# Cargador_RasPi-BplusHAT_CamSlot.net
KiCad netlist of a schematic drawn in EAGLE
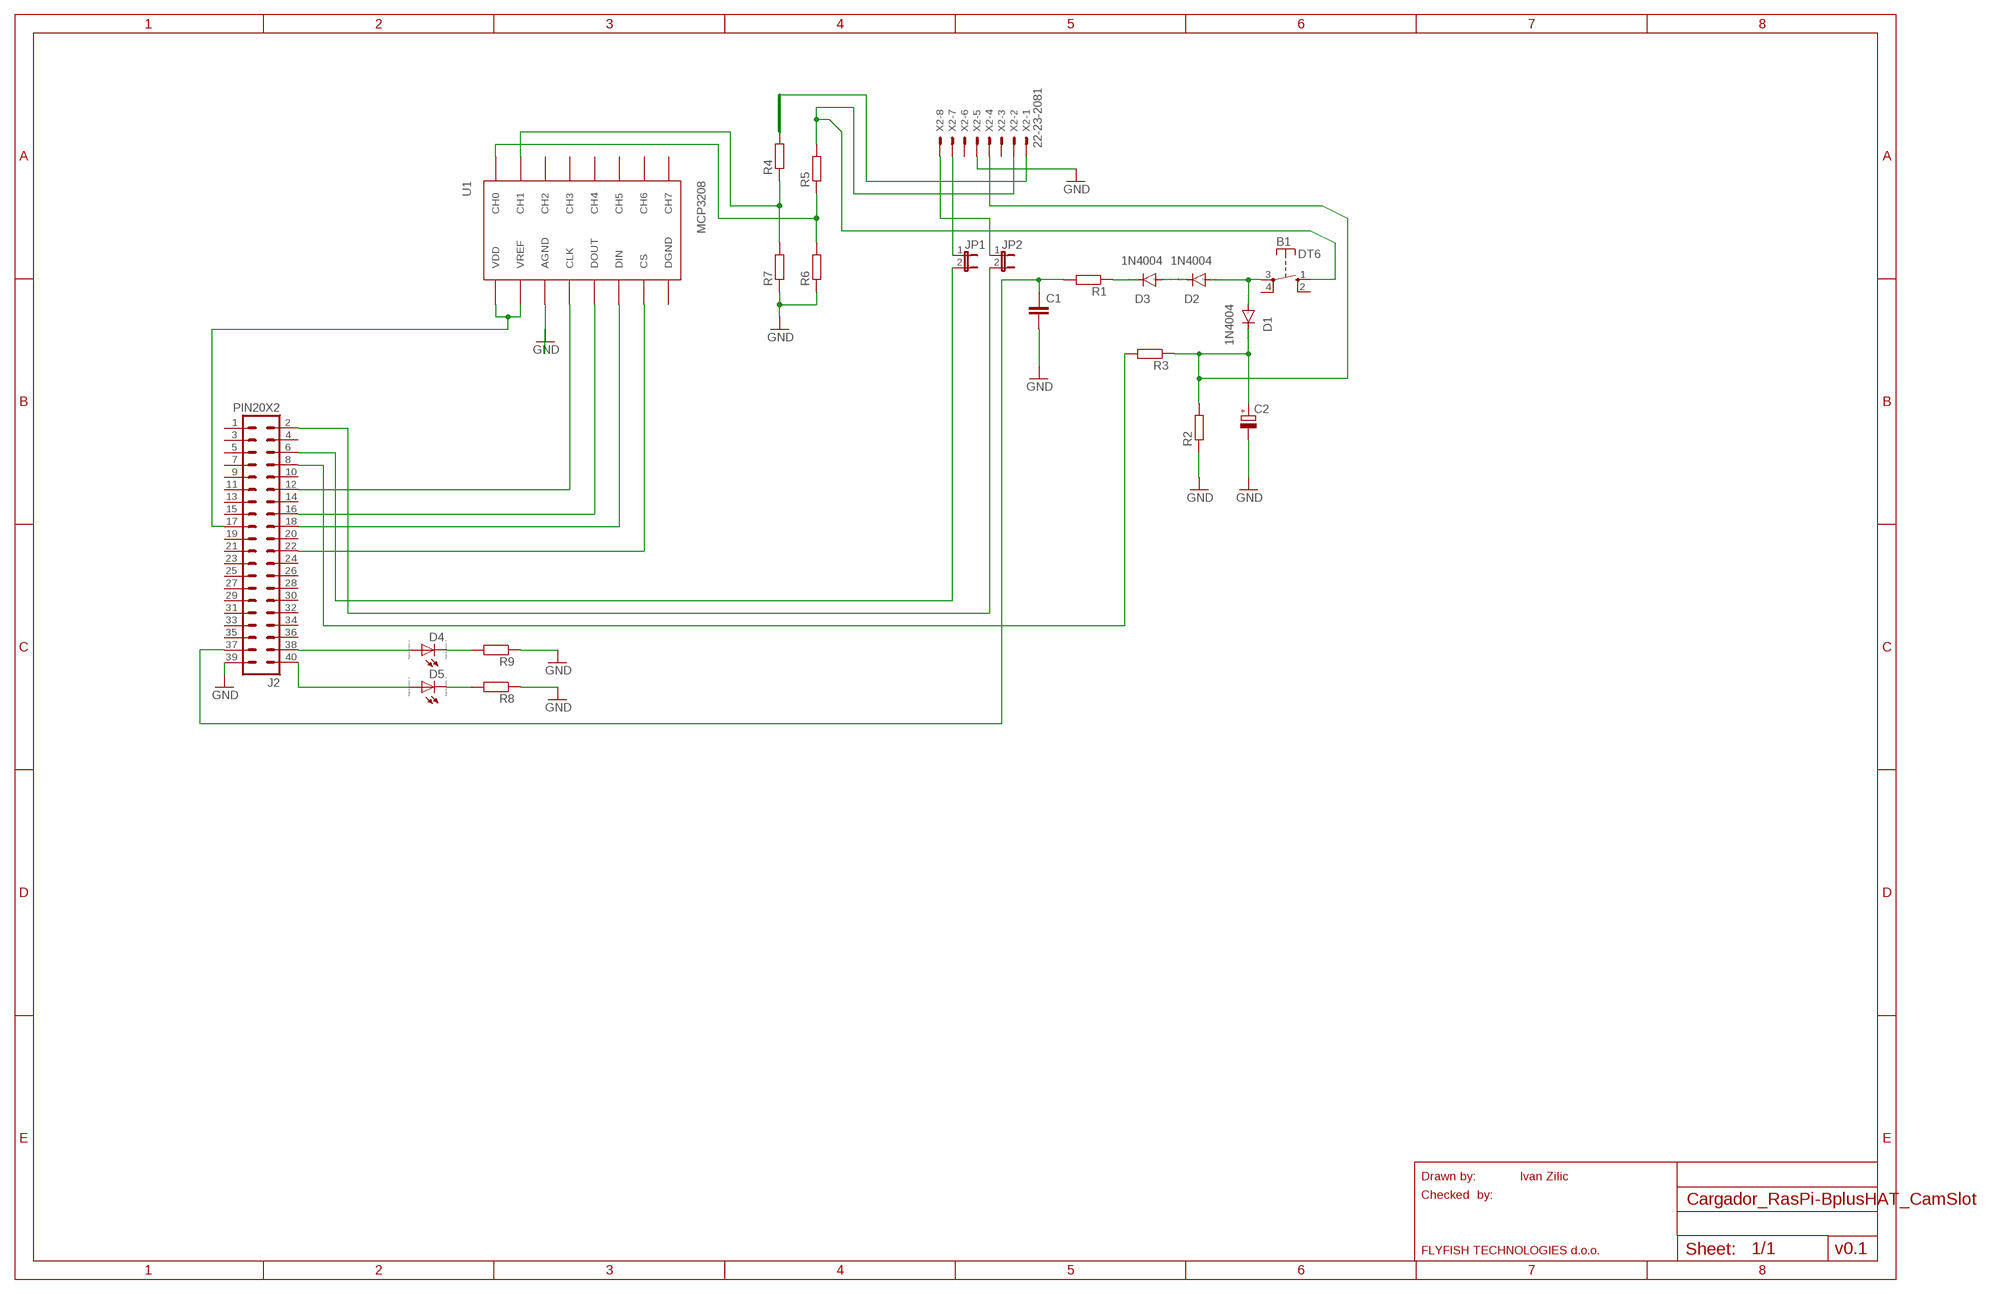
[diagram p0: schematic, sheet 1]

(export (version "E")
  (design (tool "Eeschema 10.0.6"))
  (components
    (comp (ref "B1")
      (value "DT6")
      (footprint "eagle-import:DT6")
      (libsource (lib "eagle-import") (part "DT6"))
    )
    (comp (ref "C1")
      (value "C2.5/2")
      (footprint "eagle-import:C2.5-2")
      (libsource (lib "eagle-import") (part "C2.5/2"))
    )
    (comp (ref "C2")
      (value "CPOL-EUE5-4")
      (footprint "eagle-import:E5-4")
      (libsource (lib "eagle-import") (part "CPOL-EUE5-4"))
    )
    (comp (ref "D1")
      (value "1N4004")
      (footprint "eagle-import:DO41-10")
      (libsource (lib "eagle-import") (part "1N4004"))
    )
    (comp (ref "D2")
      (value "1N4004")
      (footprint "eagle-import:DO41-10")
      (libsource (lib "eagle-import") (part "1N4004"))
    )
    (comp (ref "D3")
      (value "1N4004")
      (footprint "eagle-import:DO41-10")
      (libsource (lib "eagle-import") (part "1N4004"))
    )
    (comp (ref "D4")
      (value "LED_ELD260")
      (footprint "eagle-import:LED_LD260")
      (libsource (lib "eagle-import") (part "LED_ELD260"))
    )
    (comp (ref "D5")
      (value "LED_ELD260")
      (footprint "eagle-import:LED_LD260")
      (libsource (lib "eagle-import") (part "LED_ELD260"))
    )
    (comp (ref "J2")
      (value "PIN20X2")
      (footprint "eagle-import:PIN_20X2")
      (libsource (lib "eagle-import") (part "PIN20X2"))
    )
    (comp (ref "JP1")
      (value "JP1E")
      (footprint "eagle-import:JP1")
      (libsource (lib "eagle-import") (part "JP1E"))
    )
    (comp (ref "JP2")
      (value "JP1E")
      (footprint "eagle-import:JP1")
      (libsource (lib "eagle-import") (part "JP1E"))
    )
    (comp (ref "R1")
      (value "R-EU_0207/10")
      (footprint "eagle-import:0207_10")
      (libsource (lib "eagle-import") (part "R-EU_0207/10"))
    )
    (comp (ref "R2")
      (value "R-EU_0207/10")
      (footprint "eagle-import:0207_10")
      (libsource (lib "eagle-import") (part "R-EU_0207/10"))
    )
    (comp (ref "R3")
      (value "R-EU_0207/10")
      (footprint "eagle-import:0207_10")
      (libsource (lib "eagle-import") (part "R-EU_0207/10"))
    )
    (comp (ref "R4")
      (value "R-EU_0207/10")
      (footprint "eagle-import:0207_10")
      (libsource (lib "eagle-import") (part "R-EU_0207/10"))
    )
    (comp (ref "R5")
      (value "R-EU_0207/10")
      (footprint "eagle-import:0207_10")
      (libsource (lib "eagle-import") (part "R-EU_0207/10"))
    )
    (comp (ref "R6")
      (value "R-EU_0207/10")
      (footprint "eagle-import:0207_10")
      (libsource (lib "eagle-import") (part "R-EU_0207/10"))
    )
    (comp (ref "R7")
      (value "R-EU_0207/10")
      (footprint "eagle-import:0207_10")
      (libsource (lib "eagle-import") (part "R-EU_0207/10"))
    )
    (comp (ref "R8")
      (value "R-EU_0207/10")
      (footprint "eagle-import:0207_10")
      (libsource (lib "eagle-import") (part "R-EU_0207/10"))
    )
    (comp (ref "R9")
      (value "R-EU_0207/10")
      (footprint "eagle-import:0207_10")
      (libsource (lib "eagle-import") (part "R-EU_0207/10"))
    )
    (comp (ref "U1")
      (value "MCP3208")
      (footprint "eagle-import:DIL16")
      (libsource (lib "eagle-import") (part "MCP3208"))
    )
    (comp (ref "X2")
      (value "22-23-2081")
      (footprint "eagle-import:22-23-2081")
      (fields (field (name "MF") "MOLEX"))
      (libsource (lib "eagle-import") (part "22-23-2081"))
    )
  )
  (nets
    (net (code "1") (name "/DGND") (class "Default")
      (node (ref "U1") (pin "DGND") (pinfunction "DGND_DGND") (pintype "power_in"))
    )
    (net (code "2") (name "GND") (class "Default")
      (node (ref "C1") (pin "2") (pinfunction "2_2") (pintype "passive"))
      (node (ref "C2") (pin "-") (pinfunction "-_-") (pintype "passive"))
      (node (ref "J2") (pin "39") (pinfunction "39_39") (pintype "passive"))
      (node (ref "R2") (pin "1") (pinfunction "1_1") (pintype "passive"))
      (node (ref "R6") (pin "1") (pinfunction "1_1") (pintype "passive"))
      (node (ref "R7") (pin "1") (pinfunction "1_1") (pintype "passive"))
      (node (ref "R8") (pin "1") (pinfunction "1_1") (pintype "passive"))
      (node (ref "R9") (pin "1") (pinfunction "1_1") (pintype "passive"))
      (node (ref "U1") (pin "AGND") (pinfunction "AGND_AGND") (pintype "power_in"))
      (node (ref "X2") (pin "5") (pinfunction "S_5") (pintype "passive"))
    )
    (net (code "3") (name "Net-(B1-P-Pad3)") (class "Default")
      (node (ref "B1") (pin "3") (pinfunction "P_3") (pintype "passive"))
      (node (ref "D1") (pin "A") (pinfunction "A_A") (pintype "passive"))
      (node (ref "D2") (pin "A") (pinfunction "A_A") (pintype "passive"))
    )
    (net (code "4") (name "Net-(C1-Pad1)") (class "Default")
      (node (ref "C1") (pin "1") (pinfunction "1_1") (pintype "passive"))
      (node (ref "J2") (pin "37") (pinfunction "37_37") (pintype "passive"))
      (node (ref "R1") (pin "2") (pinfunction "2_2") (pintype "passive"))
    )
    (net (code "5") (name "Net-(D2-PadC)") (class "Default")
      (node (ref "D2") (pin "C") (pinfunction "C_C") (pintype "passive"))
      (node (ref "D3") (pin "A") (pinfunction "A_A") (pintype "passive"))
    )
    (net (code "6") (name "Net-(D3-PadC)") (class "Default")
      (node (ref "D3") (pin "C") (pinfunction "C_C") (pintype "passive"))
      (node (ref "R1") (pin "1") (pinfunction "1_1") (pintype "passive"))
    )
    (net (code "7") (name "Net-(D4-C)") (class "Default")
      (node (ref "D4") (pin "K") (pinfunction "C_K") (pintype "passive"))
      (node (ref "R9") (pin "2") (pinfunction "2_2") (pintype "passive"))
    )
    (net (code "8") (name "Net-(D4-PadA)") (class "Default")
      (node (ref "D4") (pin "A") (pinfunction "A_A") (pintype "passive"))
      (node (ref "J2") (pin "38") (pinfunction "38_38") (pintype "passive"))
    )
    (net (code "9") (name "Net-(D5-C)") (class "Default")
      (node (ref "D5") (pin "K") (pinfunction "C_K") (pintype "passive"))
      (node (ref "R8") (pin "2") (pinfunction "2_2") (pintype "passive"))
    )
    (net (code "10") (name "Net-(D5-PadA)") (class "Default")
      (node (ref "D5") (pin "A") (pinfunction "A_A") (pintype "passive"))
      (node (ref "J2") (pin "40") (pinfunction "40_40") (pintype "passive"))
    )
    (net (code "11") (name "Net-(J2-Pad2)") (class "Default")
      (node (ref "J2") (pin "2") (pinfunction "2_2") (pintype "passive"))
      (node (ref "JP2") (pin "2") (pinfunction "2_2") (pintype "passive"))
    )
    (net (code "12") (name "Net-(J2-Pad6)") (class "Default")
      (node (ref "J2") (pin "6") (pinfunction "6_6") (pintype "passive"))
      (node (ref "JP1") (pin "2") (pinfunction "2_2") (pintype "passive"))
    )
    (net (code "13") (name "Net-(J2-Pad8)") (class "Default")
      (node (ref "J2") (pin "8") (pinfunction "8_8") (pintype "passive"))
      (node (ref "R3") (pin "2") (pinfunction "2_2") (pintype "passive"))
    )
    (net (code "14") (name "Net-(J2-Pad12)") (class "Default")
      (node (ref "J2") (pin "12") (pinfunction "12_12") (pintype "passive"))
      (node (ref "U1") (pin "CLK") (pinfunction "CLK_CLK") (pintype "input"))
    )
    (net (code "15") (name "Net-(J2-Pad16)") (class "Default")
      (node (ref "J2") (pin "16") (pinfunction "16_16") (pintype "passive"))
      (node (ref "U1") (pin "DOUT") (pinfunction "DOUT_DOUT") (pintype "output"))
    )
    (net (code "16") (name "Net-(J2-Pad17)") (class "Default")
      (node (ref "J2") (pin "17") (pinfunction "17_17") (pintype "passive"))
      (node (ref "U1") (pin "VDD") (pinfunction "VDD_VDD") (pintype "power_in"))
      (node (ref "U1") (pin "VREF") (pinfunction "VREF_VREF") (pintype "input"))
    )
    (net (code "17") (name "Net-(J2-Pad18)") (class "Default")
      (node (ref "J2") (pin "18") (pinfunction "18_18") (pintype "passive"))
      (node (ref "U1") (pin "DIN") (pinfunction "DIN_DIN") (pintype "input"))
    )
    (net (code "18") (name "Net-(J2-Pad22)") (class "Default")
      (node (ref "J2") (pin "22") (pinfunction "22_22") (pintype "passive"))
      (node (ref "U1") (pin "CS") (pinfunction "CS_CS") (pintype "input"))
    )
    (net (code "19") (name "Net-(R4-Pad1)") (class "Default")
      (node (ref "R4") (pin "1") (pinfunction "1_1") (pintype "passive"))
      (node (ref "R7") (pin "2") (pinfunction "2_2") (pintype "passive"))
      (node (ref "U1") (pin "CH1") (pinfunction "CH1_CH1") (pintype "input"))
    )
    (net (code "20") (name "Net-(R5-Pad1)") (class "Default")
      (node (ref "R5") (pin "1") (pinfunction "1_1") (pintype "passive"))
      (node (ref "R6") (pin "2") (pinfunction "2_2") (pintype "passive"))
      (node (ref "U1") (pin "CH0") (pinfunction "CH0_CH0") (pintype "input"))
    )
    (net (code "21") (name "Net-(X2A-S)") (class "Default")
      (node (ref "R4") (pin "2") (pinfunction "2_2") (pintype "passive"))
      (node (ref "X2") (pin "1") (pinfunction "S_1") (pintype "passive"))
    )
    (net (code "22") (name "Net-(X2B-S)") (class "Default")
      (node (ref "B1") (pin "1") (pinfunction "S_1") (pintype "passive"))
      (node (ref "R5") (pin "2") (pinfunction "2_2") (pintype "passive"))
      (node (ref "X2") (pin "2") (pinfunction "S_2") (pintype "passive"))
    )
    (net (code "23") (name "Net-(X2D-S)") (class "Default")
      (node (ref "C2") (pin "+") (pinfunction "+_+") (pintype "passive"))
      (node (ref "D1") (pin "C") (pinfunction "C_C") (pintype "passive"))
      (node (ref "R2") (pin "2") (pinfunction "2_2") (pintype "passive"))
      (node (ref "R3") (pin "1") (pinfunction "1_1") (pintype "passive"))
      (node (ref "X2") (pin "4") (pinfunction "S_4") (pintype "passive"))
    )
    (net (code "24") (name "Net-(X2G-S)") (class "Default")
      (node (ref "JP1") (pin "1") (pinfunction "1_1") (pintype "passive"))
      (node (ref "X2") (pin "7") (pinfunction "S_7") (pintype "passive"))
    )
    (net (code "25") (name "Net-(X2H-S)") (class "Default")
      (node (ref "JP2") (pin "1") (pinfunction "1_1") (pintype "passive"))
      (node (ref "X2") (pin "8") (pinfunction "S_8") (pintype "passive"))
    )
    (net (code "26") (name "unconnected-(B1-P-Pad4)") (class "Default")
      (node (ref "B1") (pin "4") (pinfunction "P_4") (pintype "passive"))
    )
    (net (code "27") (name "unconnected-(B1-S-Pad2)") (class "Default")
      (node (ref "B1") (pin "2") (pinfunction "S_2") (pintype "passive"))
    )
    (net (code "28") (name "unconnected-(J2-Pad1)") (class "Default")
      (node (ref "J2") (pin "1") (pinfunction "1_1") (pintype "passive"))
    )
    (net (code "29") (name "unconnected-(J2-Pad3)") (class "Default")
      (node (ref "J2") (pin "3") (pinfunction "3_3") (pintype "passive"))
    )
    (net (code "30") (name "unconnected-(J2-Pad4)") (class "Default")
      (node (ref "J2") (pin "4") (pinfunction "4_4") (pintype "passive"))
    )
    (net (code "31") (name "unconnected-(J2-Pad5)") (class "Default")
      (node (ref "J2") (pin "5") (pinfunction "5_5") (pintype "passive"))
    )
    (net (code "32") (name "unconnected-(J2-Pad7)") (class "Default")
      (node (ref "J2") (pin "7") (pinfunction "7_7") (pintype "passive"))
    )
    (net (code "33") (name "unconnected-(J2-Pad9)") (class "Default")
      (node (ref "J2") (pin "9") (pinfunction "9_9") (pintype "passive"))
    )
    (net (code "34") (name "unconnected-(J2-Pad10)") (class "Default")
      (node (ref "J2") (pin "10") (pinfunction "10_10") (pintype "passive"))
    )
    (net (code "35") (name "unconnected-(J2-Pad11)") (class "Default")
      (node (ref "J2") (pin "11") (pinfunction "11_11") (pintype "passive"))
    )
    (net (code "36") (name "unconnected-(J2-Pad13)") (class "Default")
      (node (ref "J2") (pin "13") (pinfunction "13_13") (pintype "passive"))
    )
    (net (code "37") (name "unconnected-(J2-Pad14)") (class "Default")
      (node (ref "J2") (pin "14") (pinfunction "14_14") (pintype "passive"))
    )
    (net (code "38") (name "unconnected-(J2-Pad15)") (class "Default")
      (node (ref "J2") (pin "15") (pinfunction "15_15") (pintype "passive"))
    )
    (net (code "39") (name "unconnected-(J2-Pad19)") (class "Default")
      (node (ref "J2") (pin "19") (pinfunction "19_19") (pintype "passive"))
    )
    (net (code "40") (name "unconnected-(J2-Pad20)") (class "Default")
      (node (ref "J2") (pin "20") (pinfunction "20_20") (pintype "passive"))
    )
    (net (code "41") (name "unconnected-(J2-Pad21)") (class "Default")
      (node (ref "J2") (pin "21") (pinfunction "21_21") (pintype "passive"))
    )
    (net (code "42") (name "unconnected-(J2-Pad23)") (class "Default")
      (node (ref "J2") (pin "23") (pinfunction "23_23") (pintype "passive"))
    )
    (net (code "43") (name "unconnected-(J2-Pad24)") (class "Default")
      (node (ref "J2") (pin "24") (pinfunction "24_24") (pintype "passive"))
    )
    (net (code "44") (name "unconnected-(J2-Pad25)") (class "Default")
      (node (ref "J2") (pin "25") (pinfunction "25_25") (pintype "passive"))
    )
    (net (code "45") (name "unconnected-(J2-Pad26)") (class "Default")
      (node (ref "J2") (pin "26") (pinfunction "26_26") (pintype "passive"))
    )
    (net (code "46") (name "unconnected-(J2-Pad27)") (class "Default")
      (node (ref "J2") (pin "27") (pinfunction "27_27") (pintype "passive"))
    )
    (net (code "47") (name "unconnected-(J2-Pad28)") (class "Default")
      (node (ref "J2") (pin "28") (pinfunction "28_28") (pintype "passive"))
    )
    (net (code "48") (name "unconnected-(J2-Pad29)") (class "Default")
      (node (ref "J2") (pin "29") (pinfunction "29_29") (pintype "passive"))
    )
    (net (code "49") (name "unconnected-(J2-Pad30)") (class "Default")
      (node (ref "J2") (pin "30") (pinfunction "30_30") (pintype "passive"))
    )
    (net (code "50") (name "unconnected-(J2-Pad31)") (class "Default")
      (node (ref "J2") (pin "31") (pinfunction "31_31") (pintype "passive"))
    )
    (net (code "51") (name "unconnected-(J2-Pad32)") (class "Default")
      (node (ref "J2") (pin "32") (pinfunction "32_32") (pintype "passive"))
    )
    (net (code "52") (name "unconnected-(J2-Pad33)") (class "Default")
      (node (ref "J2") (pin "33") (pinfunction "33_33") (pintype "passive"))
    )
    (net (code "53") (name "unconnected-(J2-Pad34)") (class "Default")
      (node (ref "J2") (pin "34") (pinfunction "34_34") (pintype "passive"))
    )
    (net (code "54") (name "unconnected-(J2-Pad35)") (class "Default")
      (node (ref "J2") (pin "35") (pinfunction "35_35") (pintype "passive"))
    )
    (net (code "55") (name "unconnected-(J2-Pad36)") (class "Default")
      (node (ref "J2") (pin "36") (pinfunction "36_36") (pintype "passive"))
    )
    (net (code "56") (name "unconnected-(U1-PadCH2)") (class "Default")
      (node (ref "U1") (pin "CH2") (pinfunction "CH2_CH2") (pintype "input"))
    )
    (net (code "57") (name "unconnected-(U1-PadCH3)") (class "Default")
      (node (ref "U1") (pin "CH3") (pinfunction "CH3_CH3") (pintype "input"))
    )
    (net (code "58") (name "unconnected-(U1-PadCH4)") (class "Default")
      (node (ref "U1") (pin "CH4") (pinfunction "CH4_CH4") (pintype "input"))
    )
    (net (code "59") (name "unconnected-(U1-PadCH5)") (class "Default")
      (node (ref "U1") (pin "CH5") (pinfunction "CH5_CH5") (pintype "input"))
    )
    (net (code "60") (name "unconnected-(U1-PadCH6)") (class "Default")
      (node (ref "U1") (pin "CH6") (pinfunction "CH6_CH6") (pintype "input"))
    )
    (net (code "61") (name "unconnected-(U1-PadCH7)") (class "Default")
      (node (ref "U1") (pin "CH7") (pinfunction "CH7_CH7") (pintype "input"))
    )
    (net (code "62") (name "unconnected-(X2C-S-Pad3)") (class "Default")
      (node (ref "X2") (pin "3") (pinfunction "S_3") (pintype "passive"))
    )
    (net (code "63") (name "unconnected-(X2F-S-Pad6)") (class "Default")
      (node (ref "X2") (pin "6") (pinfunction "S_6") (pintype "passive"))
    )
  )
)
